# fpga21-serdes-power.net
KiCad netlist of a schematic drawn in Altium Designer
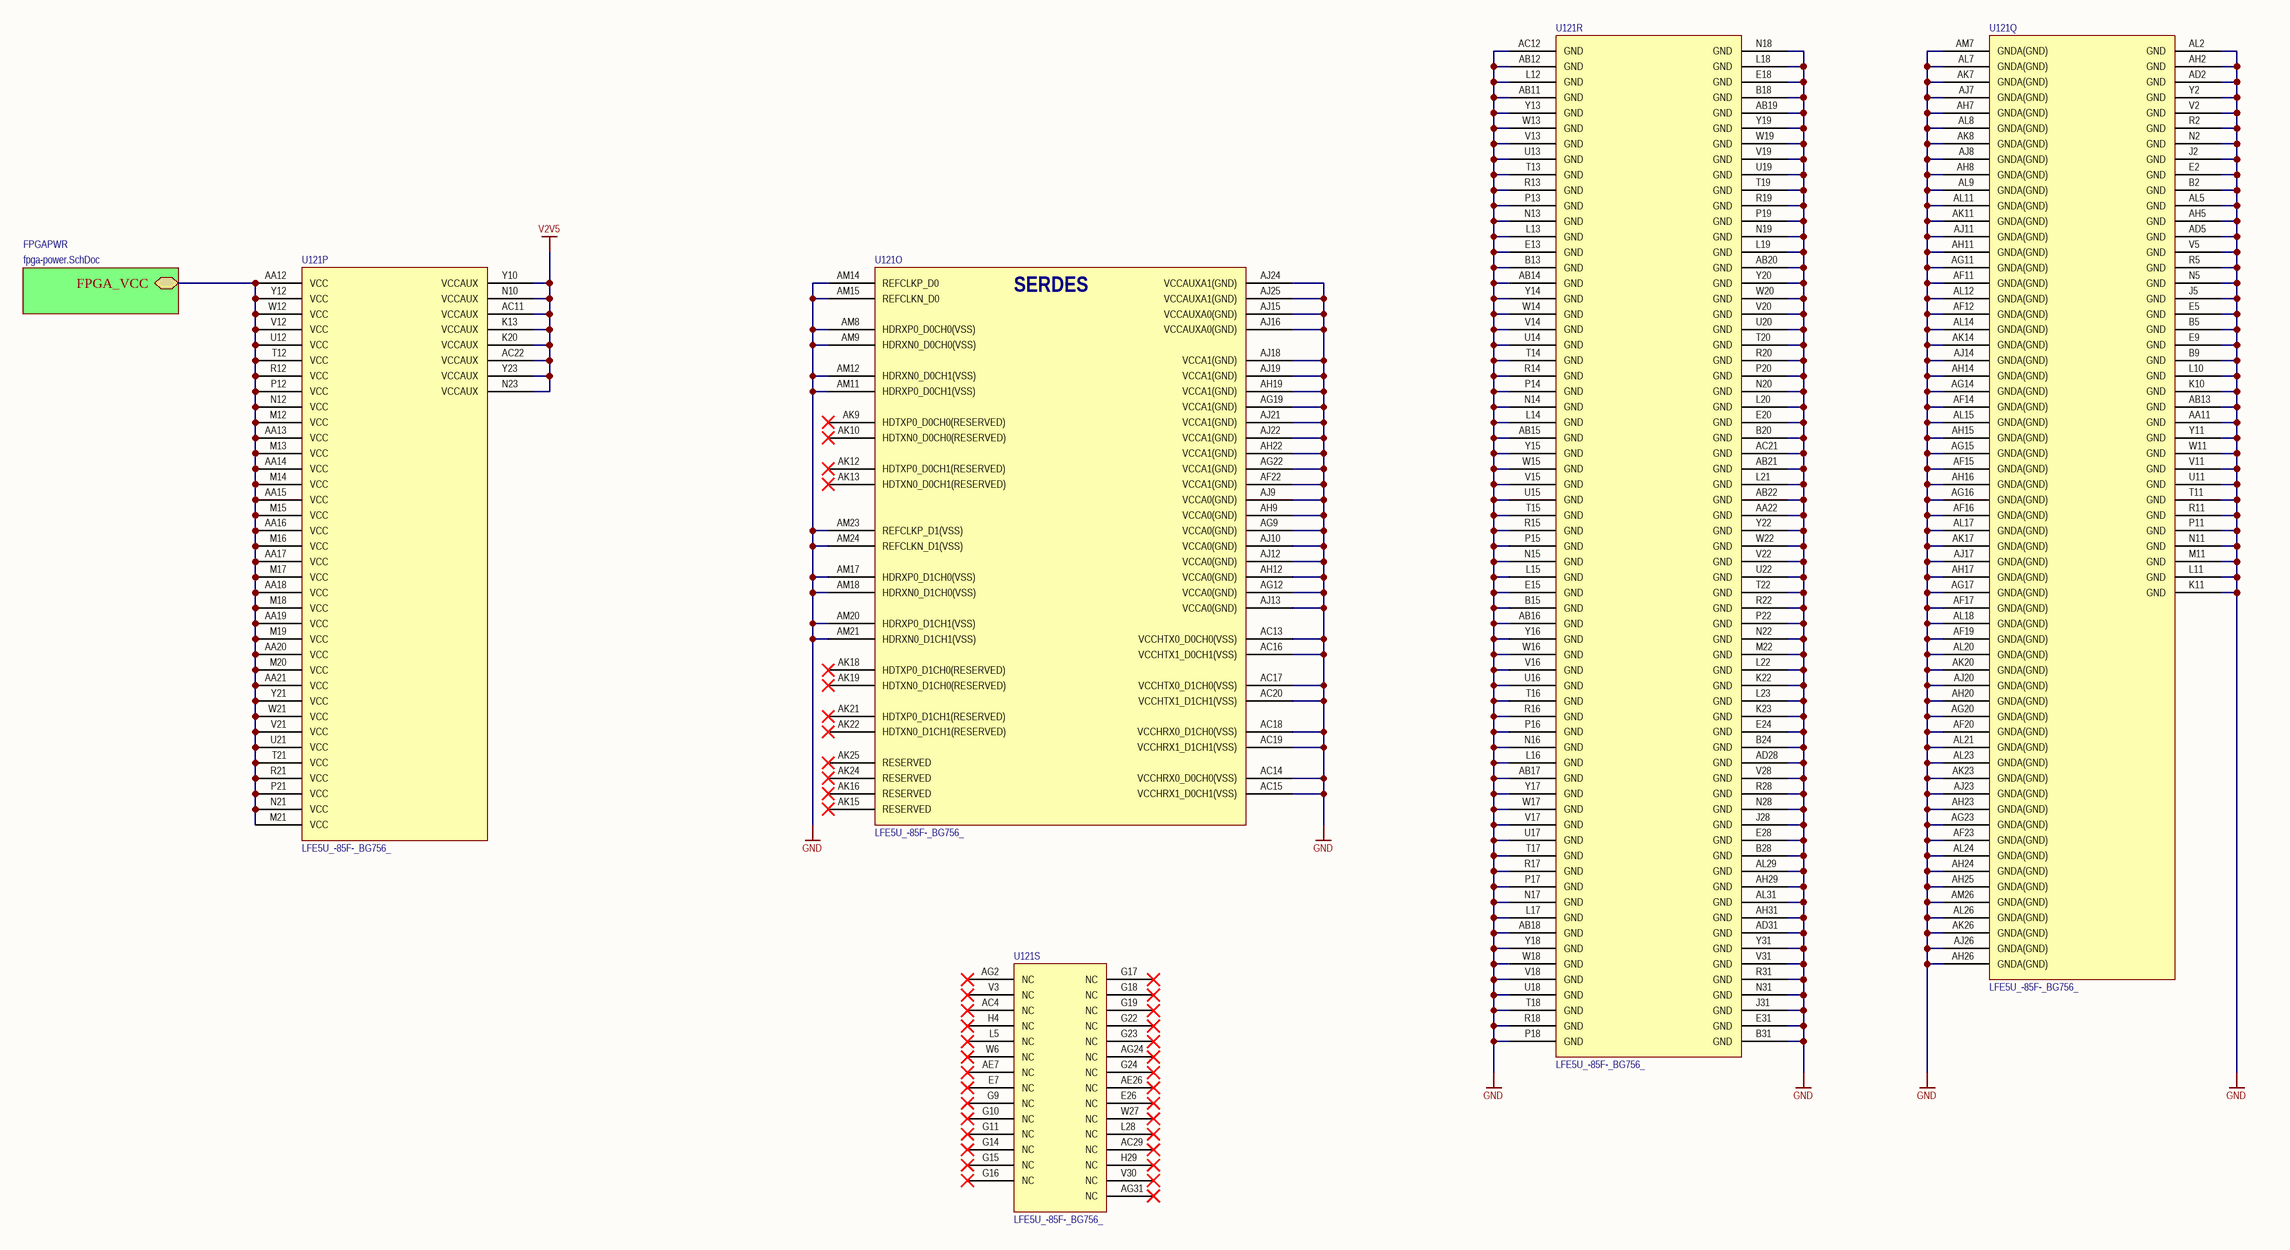
[diagram p0: fpga21-serdes-power.SchDoc]

(export (version "E")
  (design (tool "Eeschema 10.0.6"))
  (components
    (comp (ref "U121")
      (value "LFE5U_-85F-_BG756_")
      (footprint "lattice:caBGA756")
      (description "ECP5 FPGA, 85k LUT, 756-caBGA")
      (fields (field (name "MANUFACTURER") "Lattice Semiconductor"))
      (libsource (lib "lattice") (part "LFE5U_-85F-_BG756_"))
    )
  )
  (nets
    (net (code "1") (name "/FPGA_VCC") (class "Default")
      (node (ref "U121") (pin "AA12") (pinfunction "VCC_AA12") (pintype "power_in"))
      (node (ref "U121") (pin "AA13") (pinfunction "VCC_AA13") (pintype "power_in"))
      (node (ref "U121") (pin "AA14") (pinfunction "VCC_AA14") (pintype "power_in"))
      (node (ref "U121") (pin "AA15") (pinfunction "VCC_AA15") (pintype "power_in"))
      (node (ref "U121") (pin "AA16") (pinfunction "VCC_AA16") (pintype "power_in"))
      (node (ref "U121") (pin "AA17") (pinfunction "VCC_AA17") (pintype "power_in"))
      (node (ref "U121") (pin "AA18") (pinfunction "VCC_AA18") (pintype "power_in"))
      (node (ref "U121") (pin "AA19") (pinfunction "VCC_AA19") (pintype "power_in"))
      (node (ref "U121") (pin "AA20") (pinfunction "VCC_AA20") (pintype "power_in"))
      (node (ref "U121") (pin "AA21") (pinfunction "VCC_AA21") (pintype "power_in"))
      (node (ref "U121") (pin "M12") (pinfunction "VCC_M12") (pintype "power_in"))
      (node (ref "U121") (pin "M13") (pinfunction "VCC_M13") (pintype "power_in"))
      (node (ref "U121") (pin "M14") (pinfunction "VCC_M14") (pintype "power_in"))
      (node (ref "U121") (pin "M15") (pinfunction "VCC_M15") (pintype "power_in"))
      (node (ref "U121") (pin "M16") (pinfunction "VCC_M16") (pintype "power_in"))
      (node (ref "U121") (pin "M17") (pinfunction "VCC_M17") (pintype "power_in"))
      (node (ref "U121") (pin "M18") (pinfunction "VCC_M18") (pintype "power_in"))
      (node (ref "U121") (pin "M19") (pinfunction "VCC_M19") (pintype "power_in"))
      (node (ref "U121") (pin "M20") (pinfunction "VCC_M20") (pintype "power_in"))
      (node (ref "U121") (pin "M21") (pinfunction "VCC_M21") (pintype "power_in"))
      (node (ref "U121") (pin "N12") (pinfunction "VCC_N12") (pintype "power_in"))
      (node (ref "U121") (pin "N21") (pinfunction "VCC_N21") (pintype "power_in"))
      (node (ref "U121") (pin "P12") (pinfunction "VCC_P12") (pintype "power_in"))
      (node (ref "U121") (pin "P21") (pinfunction "VCC_P21") (pintype "power_in"))
      (node (ref "U121") (pin "R12") (pinfunction "VCC_R12") (pintype "power_in"))
      (node (ref "U121") (pin "R21") (pinfunction "VCC_R21") (pintype "power_in"))
      (node (ref "U121") (pin "T12") (pinfunction "VCC_T12") (pintype "power_in"))
      (node (ref "U121") (pin "T21") (pinfunction "VCC_T21") (pintype "power_in"))
      (node (ref "U121") (pin "U12") (pinfunction "VCC_U12") (pintype "power_in"))
      (node (ref "U121") (pin "U21") (pinfunction "VCC_U21") (pintype "power_in"))
      (node (ref "U121") (pin "V12") (pinfunction "VCC_V12") (pintype "power_in"))
      (node (ref "U121") (pin "V21") (pinfunction "VCC_V21") (pintype "power_in"))
      (node (ref "U121") (pin "W12") (pinfunction "VCC_W12") (pintype "power_in"))
      (node (ref "U121") (pin "W21") (pinfunction "VCC_W21") (pintype "power_in"))
      (node (ref "U121") (pin "Y12") (pinfunction "VCC_Y12") (pintype "power_in"))
      (node (ref "U121") (pin "Y21") (pinfunction "VCC_Y21") (pintype "power_in"))
    )
    (net (code "2") (name "GND") (class "Default")
      (node (ref "U121") (pin "AA11") (pinfunction "GND_AA11") (pintype "power_in"))
      (node (ref "U121") (pin "AA22") (pinfunction "GND_AA22") (pintype "power_in"))
      (node (ref "U121") (pin "AB11") (pinfunction "GND_AB11") (pintype "power_in"))
      (node (ref "U121") (pin "AB12") (pinfunction "GND_AB12") (pintype "power_in"))
      (node (ref "U121") (pin "AB13") (pinfunction "GND_AB13") (pintype "power_in"))
      (node (ref "U121") (pin "AB14") (pinfunction "GND_AB14") (pintype "power_in"))
      (node (ref "U121") (pin "AB15") (pinfunction "GND_AB15") (pintype "power_in"))
      (node (ref "U121") (pin "AB16") (pinfunction "GND_AB16") (pintype "power_in"))
      (node (ref "U121") (pin "AB17") (pinfunction "GND_AB17") (pintype "power_in"))
      (node (ref "U121") (pin "AB18") (pinfunction "GND_AB18") (pintype "power_in"))
      (node (ref "U121") (pin "AB19") (pinfunction "GND_AB19") (pintype "power_in"))
      (node (ref "U121") (pin "AB20") (pinfunction "GND_AB20") (pintype "power_in"))
      (node (ref "U121") (pin "AB21") (pinfunction "GND_AB21") (pintype "power_in"))
      (node (ref "U121") (pin "AB22") (pinfunction "GND_AB22") (pintype "power_in"))
      (node (ref "U121") (pin "AC12") (pinfunction "GND_AC12") (pintype "power_in"))
      (node (ref "U121") (pin "AC13") (pinfunction "VCCHTX0_D0CH0(VSS)_AC13") (pintype "power_in"))
      (node (ref "U121") (pin "AC14") (pinfunction "VCCHRX0_D0CH0(VSS)_AC14") (pintype "power_in"))
      (node (ref "U121") (pin "AC15") (pinfunction "VCCHRX1_D0CH1(VSS)_AC15") (pintype "power_in"))
      (node (ref "U121") (pin "AC16") (pinfunction "VCCHTX1_D0CH1(VSS)_AC16") (pintype "power_in"))
      (node (ref "U121") (pin "AC17") (pinfunction "VCCHTX0_D1CH0(VSS)_AC17") (pintype "power_in"))
      (node (ref "U121") (pin "AC18") (pinfunction "VCCHRX0_D1CH0(VSS)_AC18") (pintype "power_in"))
      (node (ref "U121") (pin "AC19") (pinfunction "VCCHRX1_D1CH1(VSS)_AC19") (pintype "power_in"))
      (node (ref "U121") (pin "AC20") (pinfunction "VCCHTX1_D1CH1(VSS)_AC20") (pintype "power_in"))
      (node (ref "U121") (pin "AC21") (pinfunction "GND_AC21") (pintype "power_in"))
      (node (ref "U121") (pin "AD2") (pinfunction "GND_AD2") (pintype "power_in"))
      (node (ref "U121") (pin "AD28") (pinfunction "GND_AD28") (pintype "power_in"))
      (node (ref "U121") (pin "AD31") (pinfunction "GND_AD31") (pintype "power_in"))
      (node (ref "U121") (pin "AD5") (pinfunction "GND_AD5") (pintype "power_in"))
      (node (ref "U121") (pin "AF11") (pinfunction "GNDA(GND)_AF11") (pintype "power_in"))
      (node (ref "U121") (pin "AF12") (pinfunction "GNDA(GND)_AF12") (pintype "power_in"))
      (node (ref "U121") (pin "AF14") (pinfunction "GNDA(GND)_AF14") (pintype "power_in"))
      (node (ref "U121") (pin "AF15") (pinfunction "GNDA(GND)_AF15") (pintype "power_in"))
      (node (ref "U121") (pin "AF16") (pinfunction "GNDA(GND)_AF16") (pintype "power_in"))
      (node (ref "U121") (pin "AF17") (pinfunction "GNDA(GND)_AF17") (pintype "power_in"))
      (node (ref "U121") (pin "AF19") (pinfunction "GNDA(GND)_AF19") (pintype "power_in"))
      (node (ref "U121") (pin "AF20") (pinfunction "GNDA(GND)_AF20") (pintype "power_in"))
      (node (ref "U121") (pin "AF22") (pinfunction "VCCA1(GND)_AF22") (pintype "power_in"))
      (node (ref "U121") (pin "AF23") (pinfunction "GNDA(GND)_AF23") (pintype "power_in"))
      (node (ref "U121") (pin "AG11") (pinfunction "GNDA(GND)_AG11") (pintype "power_in"))
      (node (ref "U121") (pin "AG12") (pinfunction "VCCA0(GND)_AG12") (pintype "power_in"))
      (node (ref "U121") (pin "AG14") (pinfunction "GNDA(GND)_AG14") (pintype "power_in"))
      (node (ref "U121") (pin "AG15") (pinfunction "GNDA(GND)_AG15") (pintype "power_in"))
      (node (ref "U121") (pin "AG16") (pinfunction "GNDA(GND)_AG16") (pintype "power_in"))
      (node (ref "U121") (pin "AG17") (pinfunction "GNDA(GND)_AG17") (pintype "power_in"))
      (node (ref "U121") (pin "AG19") (pinfunction "VCCA1(GND)_AG19") (pintype "power_in"))
      (node (ref "U121") (pin "AG20") (pinfunction "GNDA(GND)_AG20") (pintype "power_in"))
      (node (ref "U121") (pin "AG22") (pinfunction "VCCA1(GND)_AG22") (pintype "power_in"))
      (node (ref "U121") (pin "AG23") (pinfunction "GNDA(GND)_AG23") (pintype "power_in"))
      (node (ref "U121") (pin "AG9") (pinfunction "VCCA0(GND)_AG9") (pintype "power_in"))
      (node (ref "U121") (pin "AH11") (pinfunction "GNDA(GND)_AH11") (pintype "power_in"))
      (node (ref "U121") (pin "AH12") (pinfunction "VCCA0(GND)_AH12") (pintype "power_in"))
      (node (ref "U121") (pin "AH14") (pinfunction "GNDA(GND)_AH14") (pintype "power_in"))
      (node (ref "U121") (pin "AH15") (pinfunction "GNDA(GND)_AH15") (pintype "power_in"))
      (node (ref "U121") (pin "AH16") (pinfunction "GNDA(GND)_AH16") (pintype "power_in"))
      (node (ref "U121") (pin "AH17") (pinfunction "GNDA(GND)_AH17") (pintype "power_in"))
      (node (ref "U121") (pin "AH19") (pinfunction "VCCA1(GND)_AH19") (pintype "power_in"))
      (node (ref "U121") (pin "AH2") (pinfunction "GND_AH2") (pintype "power_in"))
      (node (ref "U121") (pin "AH20") (pinfunction "GNDA(GND)_AH20") (pintype "power_in"))
      (node (ref "U121") (pin "AH22") (pinfunction "VCCA1(GND)_AH22") (pintype "power_in"))
      (node (ref "U121") (pin "AH23") (pinfunction "GNDA(GND)_AH23") (pintype "power_in"))
      (node (ref "U121") (pin "AH24") (pinfunction "GNDA(GND)_AH24") (pintype "power_in"))
      (node (ref "U121") (pin "AH25") (pinfunction "GNDA(GND)_AH25") (pintype "power_in"))
      (node (ref "U121") (pin "AH26") (pinfunction "GNDA(GND)_AH26") (pintype "power_in"))
      (node (ref "U121") (pin "AH29") (pinfunction "GND_AH29") (pintype "power_in"))
      (node (ref "U121") (pin "AH31") (pinfunction "GND_AH31") (pintype "power_in"))
      (node (ref "U121") (pin "AH5") (pinfunction "GND_AH5") (pintype "power_in"))
      (node (ref "U121") (pin "AH7") (pinfunction "GNDA(GND)_AH7") (pintype "power_in"))
      (node (ref "U121") (pin "AH8") (pinfunction "GNDA(GND)_AH8") (pintype "power_in"))
      (node (ref "U121") (pin "AH9") (pinfunction "VCCA0(GND)_AH9") (pintype "power_in"))
      (node (ref "U121") (pin "AJ10") (pinfunction "VCCA0(GND)_AJ10") (pintype "power_in"))
      (node (ref "U121") (pin "AJ11") (pinfunction "GNDA(GND)_AJ11") (pintype "power_in"))
      (node (ref "U121") (pin "AJ12") (pinfunction "VCCA0(GND)_AJ12") (pintype "power_in"))
      (node (ref "U121") (pin "AJ13") (pinfunction "VCCA0(GND)_AJ13") (pintype "power_in"))
      (node (ref "U121") (pin "AJ14") (pinfunction "GNDA(GND)_AJ14") (pintype "power_in"))
      (node (ref "U121") (pin "AJ15") (pinfunction "VCCAUXA0(GND)_AJ15") (pintype "power_in"))
      (node (ref "U121") (pin "AJ16") (pinfunction "VCCAUXA0(GND)_AJ16") (pintype "power_in"))
      (node (ref "U121") (pin "AJ17") (pinfunction "GNDA(GND)_AJ17") (pintype "power_in"))
      (node (ref "U121") (pin "AJ18") (pinfunction "VCCA1(GND)_AJ18") (pintype "power_in"))
      (node (ref "U121") (pin "AJ19") (pinfunction "VCCA1(GND)_AJ19") (pintype "power_in"))
      (node (ref "U121") (pin "AJ20") (pinfunction "GNDA(GND)_AJ20") (pintype "power_in"))
      (node (ref "U121") (pin "AJ21") (pinfunction "VCCA1(GND)_AJ21") (pintype "power_in"))
      (node (ref "U121") (pin "AJ22") (pinfunction "VCCA1(GND)_AJ22") (pintype "power_in"))
      (node (ref "U121") (pin "AJ23") (pinfunction "GNDA(GND)_AJ23") (pintype "power_in"))
      (node (ref "U121") (pin "AJ24") (pinfunction "VCCAUXA1(GND)_AJ24") (pintype "power_in"))
      (node (ref "U121") (pin "AJ25") (pinfunction "VCCAUXA1(GND)_AJ25") (pintype "power_in"))
      (node (ref "U121") (pin "AJ26") (pinfunction "GNDA(GND)_AJ26") (pintype "power_in"))
      (node (ref "U121") (pin "AJ7") (pinfunction "GNDA(GND)_AJ7") (pintype "power_in"))
      (node (ref "U121") (pin "AJ8") (pinfunction "GNDA(GND)_AJ8") (pintype "power_in"))
      (node (ref "U121") (pin "AJ9") (pinfunction "VCCA0(GND)_AJ9") (pintype "power_in"))
      (node (ref "U121") (pin "AK11") (pinfunction "GNDA(GND)_AK11") (pintype "power_in"))
      (node (ref "U121") (pin "AK14") (pinfunction "GNDA(GND)_AK14") (pintype "power_in"))
      (node (ref "U121") (pin "AK17") (pinfunction "GNDA(GND)_AK17") (pintype "power_in"))
      (node (ref "U121") (pin "AK20") (pinfunction "GNDA(GND)_AK20") (pintype "power_in"))
      (node (ref "U121") (pin "AK23") (pinfunction "GNDA(GND)_AK23") (pintype "power_in"))
      (node (ref "U121") (pin "AK26") (pinfunction "GNDA(GND)_AK26") (pintype "power_in"))
      (node (ref "U121") (pin "AK7") (pinfunction "GNDA(GND)_AK7") (pintype "power_in"))
      (node (ref "U121") (pin "AK8") (pinfunction "GNDA(GND)_AK8") (pintype "power_in"))
      (node (ref "U121") (pin "AL11") (pinfunction "GNDA(GND)_AL11") (pintype "power_in"))
      (node (ref "U121") (pin "AL12") (pinfunction "GNDA(GND)_AL12") (pintype "power_in"))
      (node (ref "U121") (pin "AL14") (pinfunction "GNDA(GND)_AL14") (pintype "power_in"))
      (node (ref "U121") (pin "AL15") (pinfunction "GNDA(GND)_AL15") (pintype "power_in"))
      (node (ref "U121") (pin "AL17") (pinfunction "GNDA(GND)_AL17") (pintype "power_in"))
      (node (ref "U121") (pin "AL18") (pinfunction "GNDA(GND)_AL18") (pintype "power_in"))
      (node (ref "U121") (pin "AL2") (pinfunction "GND_AL2") (pintype "power_in"))
      (node (ref "U121") (pin "AL20") (pinfunction "GNDA(GND)_AL20") (pintype "power_in"))
      (node (ref "U121") (pin "AL21") (pinfunction "GNDA(GND)_AL21") (pintype "power_in"))
      (node (ref "U121") (pin "AL23") (pinfunction "GNDA(GND)_AL23") (pintype "power_in"))
      (node (ref "U121") (pin "AL24") (pinfunction "GNDA(GND)_AL24") (pintype "power_in"))
      (node (ref "U121") (pin "AL26") (pinfunction "GNDA(GND)_AL26") (pintype "power_in"))
      (node (ref "U121") (pin "AL29") (pinfunction "GND_AL29") (pintype "power_in"))
      (node (ref "U121") (pin "AL31") (pinfunction "GND_AL31") (pintype "power_in"))
      (node (ref "U121") (pin "AL5") (pinfunction "GND_AL5") (pintype "power_in"))
      (node (ref "U121") (pin "AL7") (pinfunction "GNDA(GND)_AL7") (pintype "power_in"))
      (node (ref "U121") (pin "AL8") (pinfunction "GNDA(GND)_AL8") (pintype "power_in"))
      (node (ref "U121") (pin "AL9") (pinfunction "GNDA(GND)_AL9") (pintype "power_in"))
      (node (ref "U121") (pin "AM11") (pinfunction "HDRXP0_D0CH1(VSS)_AM11") (pintype "passive"))
      (node (ref "U121") (pin "AM12") (pinfunction "HDRXN0_D0CH1(VSS)_AM12") (pintype "passive"))
      (node (ref "U121") (pin "AM14") (pinfunction "REFCLKP_D0_AM14") (pintype "passive"))
      (node (ref "U121") (pin "AM15") (pinfunction "REFCLKN_D0_AM15") (pintype "passive"))
      (node (ref "U121") (pin "AM17") (pinfunction "HDRXP0_D1CH0(VSS)_AM17") (pintype "passive"))
      (node (ref "U121") (pin "AM18") (pinfunction "HDRXN0_D1CH0(VSS)_AM18") (pintype "passive"))
      (node (ref "U121") (pin "AM20") (pinfunction "HDRXP0_D1CH1(VSS)_AM20") (pintype "passive"))
      (node (ref "U121") (pin "AM21") (pinfunction "HDRXN0_D1CH1(VSS)_AM21") (pintype "passive"))
      (node (ref "U121") (pin "AM23") (pinfunction "REFCLKP_D1(VSS)_AM23") (pintype "passive"))
      (node (ref "U121") (pin "AM24") (pinfunction "REFCLKN_D1(VSS)_AM24") (pintype "passive"))
      (node (ref "U121") (pin "AM26") (pinfunction "GNDA(GND)_AM26") (pintype "power_in"))
      (node (ref "U121") (pin "AM7") (pinfunction "GNDA(GND)_AM7") (pintype "power_in"))
      (node (ref "U121") (pin "AM8") (pinfunction "HDRXP0_D0CH0(VSS)_AM8") (pintype "passive"))
      (node (ref "U121") (pin "AM9") (pinfunction "HDRXN0_D0CH0(VSS)_AM9") (pintype "passive"))
      (node (ref "U121") (pin "B13") (pinfunction "GND_B13") (pintype "power_in"))
      (node (ref "U121") (pin "B15") (pinfunction "GND_B15") (pintype "power_in"))
      (node (ref "U121") (pin "B18") (pinfunction "GND_B18") (pintype "power_in"))
      (node (ref "U121") (pin "B2") (pinfunction "GND_B2") (pintype "power_in"))
      (node (ref "U121") (pin "B20") (pinfunction "GND_B20") (pintype "power_in"))
      (node (ref "U121") (pin "B24") (pinfunction "GND_B24") (pintype "power_in"))
      (node (ref "U121") (pin "B28") (pinfunction "GND_B28") (pintype "power_in"))
      (node (ref "U121") (pin "B31") (pinfunction "GND_B31") (pintype "power_in"))
      (node (ref "U121") (pin "B5") (pinfunction "GND_B5") (pintype "power_in"))
      (node (ref "U121") (pin "B9") (pinfunction "GND_B9") (pintype "power_in"))
      (node (ref "U121") (pin "E13") (pinfunction "GND_E13") (pintype "power_in"))
      (node (ref "U121") (pin "E15") (pinfunction "GND_E15") (pintype "power_in"))
      (node (ref "U121") (pin "E18") (pinfunction "GND_E18") (pintype "power_in"))
      (node (ref "U121") (pin "E2") (pinfunction "GND_E2") (pintype "power_in"))
      (node (ref "U121") (pin "E20") (pinfunction "GND_E20") (pintype "power_in"))
      (node (ref "U121") (pin "E24") (pinfunction "GND_E24") (pintype "power_in"))
      (node (ref "U121") (pin "E28") (pinfunction "GND_E28") (pintype "power_in"))
      (node (ref "U121") (pin "E31") (pinfunction "GND_E31") (pintype "power_in"))
      (node (ref "U121") (pin "E5") (pinfunction "GND_E5") (pintype "power_in"))
      (node (ref "U121") (pin "E9") (pinfunction "GND_E9") (pintype "power_in"))
      (node (ref "U121") (pin "J2") (pinfunction "GND_J2") (pintype "power_in"))
      (node (ref "U121") (pin "J28") (pinfunction "GND_J28") (pintype "power_in"))
      (node (ref "U121") (pin "J31") (pinfunction "GND_J31") (pintype "power_in"))
      (node (ref "U121") (pin "J5") (pinfunction "GND_J5") (pintype "power_in"))
      (node (ref "U121") (pin "K10") (pinfunction "GND_K10") (pintype "power_in"))
      (node (ref "U121") (pin "K11") (pinfunction "GND_K11") (pintype "power_in"))
      (node (ref "U121") (pin "K22") (pinfunction "GND_K22") (pintype "power_in"))
      (node (ref "U121") (pin "K23") (pinfunction "GND_K23") (pintype "power_in"))
      (node (ref "U121") (pin "L10") (pinfunction "GND_L10") (pintype "power_in"))
      (node (ref "U121") (pin "L11") (pinfunction "GND_L11") (pintype "power_in"))
      (node (ref "U121") (pin "L12") (pinfunction "GND_L12") (pintype "power_in"))
      (node (ref "U121") (pin "L13") (pinfunction "GND_L13") (pintype "power_in"))
      (node (ref "U121") (pin "L14") (pinfunction "GND_L14") (pintype "power_in"))
      (node (ref "U121") (pin "L15") (pinfunction "GND_L15") (pintype "power_in"))
      (node (ref "U121") (pin "L16") (pinfunction "GND_L16") (pintype "power_in"))
      (node (ref "U121") (pin "L17") (pinfunction "GND_L17") (pintype "power_in"))
      (node (ref "U121") (pin "L18") (pinfunction "GND_L18") (pintype "power_in"))
      (node (ref "U121") (pin "L19") (pinfunction "GND_L19") (pintype "power_in"))
      (node (ref "U121") (pin "L20") (pinfunction "GND_L20") (pintype "power_in"))
      (node (ref "U121") (pin "L21") (pinfunction "GND_L21") (pintype "power_in"))
      (node (ref "U121") (pin "L22") (pinfunction "GND_L22") (pintype "power_in"))
      (node (ref "U121") (pin "L23") (pinfunction "GND_L23") (pintype "power_in"))
      (node (ref "U121") (pin "M11") (pinfunction "GND_M11") (pintype "power_in"))
      (node (ref "U121") (pin "M22") (pinfunction "GND_M22") (pintype "power_in"))
      (node (ref "U121") (pin "N11") (pinfunction "GND_N11") (pintype "power_in"))
      (node (ref "U121") (pin "N13") (pinfunction "GND_N13") (pintype "power_in"))
      (node (ref "U121") (pin "N14") (pinfunction "GND_N14") (pintype "power_in"))
      (node (ref "U121") (pin "N15") (pinfunction "GND_N15") (pintype "power_in"))
      (node (ref "U121") (pin "N16") (pinfunction "GND_N16") (pintype "power_in"))
      (node (ref "U121") (pin "N17") (pinfunction "GND_N17") (pintype "power_in"))
      (node (ref "U121") (pin "N18") (pinfunction "GND_N18") (pintype "power_in"))
      (node (ref "U121") (pin "N19") (pinfunction "GND_N19") (pintype "power_in"))
      (node (ref "U121") (pin "N2") (pinfunction "GND_N2") (pintype "power_in"))
      (node (ref "U121") (pin "N20") (pinfunction "GND_N20") (pintype "power_in"))
      (node (ref "U121") (pin "N22") (pinfunction "GND_N22") (pintype "power_in"))
      (node (ref "U121") (pin "N28") (pinfunction "GND_N28") (pintype "power_in"))
      (node (ref "U121") (pin "N31") (pinfunction "GND_N31") (pintype "power_in"))
      (node (ref "U121") (pin "N5") (pinfunction "GND_N5") (pintype "power_in"))
      (node (ref "U121") (pin "P11") (pinfunction "GND_P11") (pintype "power_in"))
      (node (ref "U121") (pin "P13") (pinfunction "GND_P13") (pintype "power_in"))
      (node (ref "U121") (pin "P14") (pinfunction "GND_P14") (pintype "power_in"))
      (node (ref "U121") (pin "P15") (pinfunction "GND_P15") (pintype "power_in"))
      (node (ref "U121") (pin "P16") (pinfunction "GND_P16") (pintype "power_in"))
      (node (ref "U121") (pin "P17") (pinfunction "GND_P17") (pintype "power_in"))
      (node (ref "U121") (pin "P18") (pinfunction "GND_P18") (pintype "power_in"))
      (node (ref "U121") (pin "P19") (pinfunction "GND_P19") (pintype "power_in"))
      (node (ref "U121") (pin "P20") (pinfunction "GND_P20") (pintype "power_in"))
      (node (ref "U121") (pin "P22") (pinfunction "GND_P22") (pintype "power_in"))
      (node (ref "U121") (pin "R11") (pinfunction "GND_R11") (pintype "power_in"))
      (node (ref "U121") (pin "R13") (pinfunction "GND_R13") (pintype "power_in"))
      (node (ref "U121") (pin "R14") (pinfunction "GND_R14") (pintype "power_in"))
      (node (ref "U121") (pin "R15") (pinfunction "GND_R15") (pintype "power_in"))
      (node (ref "U121") (pin "R16") (pinfunction "GND_R16") (pintype "power_in"))
      (node (ref "U121") (pin "R17") (pinfunction "GND_R17") (pintype "power_in"))
      (node (ref "U121") (pin "R18") (pinfunction "GND_R18") (pintype "power_in"))
      (node (ref "U121") (pin "R19") (pinfunction "GND_R19") (pintype "power_in"))
      (node (ref "U121") (pin "R2") (pinfunction "GND_R2") (pintype "power_in"))
      (node (ref "U121") (pin "R20") (pinfunction "GND_R20") (pintype "power_in"))
      (node (ref "U121") (pin "R22") (pinfunction "GND_R22") (pintype "power_in"))
      (node (ref "U121") (pin "R28") (pinfunction "GND_R28") (pintype "power_in"))
      (node (ref "U121") (pin "R31") (pinfunction "GND_R31") (pintype "power_in"))
      (node (ref "U121") (pin "R5") (pinfunction "GND_R5") (pintype "power_in"))
      (node (ref "U121") (pin "T11") (pinfunction "GND_T11") (pintype "power_in"))
      (node (ref "U121") (pin "T13") (pinfunction "GND_T13") (pintype "power_in"))
      (node (ref "U121") (pin "T14") (pinfunction "GND_T14") (pintype "power_in"))
      (node (ref "U121") (pin "T15") (pinfunction "GND_T15") (pintype "power_in"))
      (node (ref "U121") (pin "T16") (pinfunction "GND_T16") (pintype "power_in"))
      (node (ref "U121") (pin "T17") (pinfunction "GND_T17") (pintype "power_in"))
      (node (ref "U121") (pin "T18") (pinfunction "GND_T18") (pintype "power_in"))
      (node (ref "U121") (pin "T19") (pinfunction "GND_T19") (pintype "power_in"))
      (node (ref "U121") (pin "T20") (pinfunction "GND_T20") (pintype "power_in"))
      (node (ref "U121") (pin "T22") (pinfunction "GND_T22") (pintype "power_in"))
      (node (ref "U121") (pin "U11") (pinfunction "GND_U11") (pintype "power_in"))
      (node (ref "U121") (pin "U13") (pinfunction "GND_U13") (pintype "power_in"))
      (node (ref "U121") (pin "U14") (pinfunction "GND_U14") (pintype "power_in"))
      (node (ref "U121") (pin "U15") (pinfunction "GND_U15") (pintype "power_in"))
      (node (ref "U121") (pin "U16") (pinfunction "GND_U16") (pintype "power_in"))
      (node (ref "U121") (pin "U17") (pinfunction "GND_U17") (pintype "power_in"))
      (node (ref "U121") (pin "U18") (pinfunction "GND_U18") (pintype "power_in"))
      (node (ref "U121") (pin "U19") (pinfunction "GND_U19") (pintype "power_in"))
      (node (ref "U121") (pin "U20") (pinfunction "GND_U20") (pintype "power_in"))
      (node (ref "U121") (pin "U22") (pinfunction "GND_U22") (pintype "power_in"))
      (node (ref "U121") (pin "V11") (pinfunction "GND_V11") (pintype "power_in"))
      (node (ref "U121") (pin "V13") (pinfunction "GND_V13") (pintype "power_in"))
      (node (ref "U121") (pin "V14") (pinfunction "GND_V14") (pintype "power_in"))
      (node (ref "U121") (pin "V15") (pinfunction "GND_V15") (pintype "power_in"))
      (node (ref "U121") (pin "V16") (pinfunction "GND_V16") (pintype "power_in"))
      (node (ref "U121") (pin "V17") (pinfunction "GND_V17") (pintype "power_in"))
      (node (ref "U121") (pin "V18") (pinfunction "GND_V18") (pintype "power_in"))
      (node (ref "U121") (pin "V19") (pinfunction "GND_V19") (pintype "power_in"))
      (node (ref "U121") (pin "V2") (pinfunction "GND_V2") (pintype "power_in"))
      (node (ref "U121") (pin "V20") (pinfunction "GND_V20") (pintype "power_in"))
      (node (ref "U121") (pin "V22") (pinfunction "GND_V22") (pintype "power_in"))
      (node (ref "U121") (pin "V28") (pinfunction "GND_V28") (pintype "power_in"))
      (node (ref "U121") (pin "V31") (pinfunction "GND_V31") (pintype "power_in"))
      (node (ref "U121") (pin "V5") (pinfunction "GND_V5") (pintype "power_in"))
      (node (ref "U121") (pin "W11") (pinfunction "GND_W11") (pintype "power_in"))
      (node (ref "U121") (pin "W13") (pinfunction "GND_W13") (pintype "power_in"))
      (node (ref "U121") (pin "W14") (pinfunction "GND_W14") (pintype "power_in"))
      (node (ref "U121") (pin "W15") (pinfunction "GND_W15") (pintype "power_in"))
      (node (ref "U121") (pin "W16") (pinfunction "GND_W16") (pintype "power_in"))
      (node (ref "U121") (pin "W17") (pinfunction "GND_W17") (pintype "power_in"))
      (node (ref "U121") (pin "W18") (pinfunction "GND_W18") (pintype "power_in"))
      (node (ref "U121") (pin "W19") (pinfunction "GND_W19") (pintype "power_in"))
      (node (ref "U121") (pin "W20") (pinfunction "GND_W20") (pintype "power_in"))
      (node (ref "U121") (pin "W22") (pinfunction "GND_W22") (pintype "power_in"))
      (node (ref "U121") (pin "Y11") (pinfunction "GND_Y11") (pintype "power_in"))
      (node (ref "U121") (pin "Y13") (pinfunction "GND_Y13") (pintype "power_in"))
      (node (ref "U121") (pin "Y14") (pinfunction "GND_Y14") (pintype "power_in"))
      (node (ref "U121") (pin "Y15") (pinfunction "GND_Y15") (pintype "power_in"))
      (node (ref "U121") (pin "Y16") (pinfunction "GND_Y16") (pintype "power_in"))
      (node (ref "U121") (pin "Y17") (pinfunction "GND_Y17") (pintype "power_in"))
      (node (ref "U121") (pin "Y18") (pinfunction "GND_Y18") (pintype "power_in"))
      (node (ref "U121") (pin "Y19") (pinfunction "GND_Y19") (pintype "power_in"))
      (node (ref "U121") (pin "Y2") (pinfunction "GND_Y2") (pintype "power_in"))
      (node (ref "U121") (pin "Y20") (pinfunction "GND_Y20") (pintype "power_in"))
      (node (ref "U121") (pin "Y22") (pinfunction "GND_Y22") (pintype "power_in"))
      (node (ref "U121") (pin "Y31") (pinfunction "GND_Y31") (pintype "power_in"))
    )
    (net (code "3") (name "V2V5") (class "Default")
      (node (ref "U121") (pin "AC11") (pinfunction "VCCAUX_AC11") (pintype "power_in"))
      (node (ref "U121") (pin "AC22") (pinfunction "VCCAUX_AC22") (pintype "power_in"))
      (node (ref "U121") (pin "K13") (pinfunction "VCCAUX_K13") (pintype "power_in"))
      (node (ref "U121") (pin "K20") (pinfunction "VCCAUX_K20") (pintype "power_in"))
      (node (ref "U121") (pin "N10") (pinfunction "VCCAUX_N10") (pintype "power_in"))
      (node (ref "U121") (pin "N23") (pinfunction "VCCAUX_N23") (pintype "power_in"))
      (node (ref "U121") (pin "Y10") (pinfunction "VCCAUX_Y10") (pintype "power_in"))
      (node (ref "U121") (pin "Y23") (pinfunction "VCCAUX_Y23") (pintype "power_in"))
    )
    (net (code "4") (name "unconnected-(U121O-HDTXN0_D0CH0(RESERVED)-PadAK10)") (class "Default")
      (node (ref "U121") (pin "AK10") (pinfunction "HDTXN0_D0CH0(RESERVED)_AK10") (pintype "passive+no_connect"))
    )
    (net (code "5") (name "unconnected-(U121O-HDTXN0_D0CH1(RESERVED)-PadAK13)") (class "Default")
      (node (ref "U121") (pin "AK13") (pinfunction "HDTXN0_D0CH1(RESERVED)_AK13") (pintype "passive+no_connect"))
    )
    (net (code "6") (name "unconnected-(U121O-HDTXN0_D1CH0(RESERVED)-PadAK19)") (class "Default")
      (node (ref "U121") (pin "AK19") (pinfunction "HDTXN0_D1CH0(RESERVED)_AK19") (pintype "passive+no_connect"))
    )
    (net (code "7") (name "unconnected-(U121O-HDTXN0_D1CH1(RESERVED)-PadAK22)") (class "Default")
      (node (ref "U121") (pin "AK22") (pinfunction "HDTXN0_D1CH1(RESERVED)_AK22") (pintype "passive+no_connect"))
    )
    (net (code "8") (name "unconnected-(U121O-HDTXP0_D0CH0(RESERVED)-PadAK9)") (class "Default")
      (node (ref "U121") (pin "AK9") (pinfunction "HDTXP0_D0CH0(RESERVED)_AK9") (pintype "passive+no_connect"))
    )
    (net (code "9") (name "unconnected-(U121O-HDTXP0_D0CH1(RESERVED)-PadAK12)") (class "Default")
      (node (ref "U121") (pin "AK12") (pinfunction "HDTXP0_D0CH1(RESERVED)_AK12") (pintype "passive+no_connect"))
    )
    (net (code "10") (name "unconnected-(U121O-HDTXP0_D1CH0(RESERVED)-PadAK18)") (class "Default")
      (node (ref "U121") (pin "AK18") (pinfunction "HDTXP0_D1CH0(RESERVED)_AK18") (pintype "passive+no_connect"))
    )
    (net (code "11") (name "unconnected-(U121O-HDTXP0_D1CH1(RESERVED)-PadAK21)") (class "Default")
      (node (ref "U121") (pin "AK21") (pinfunction "HDTXP0_D1CH1(RESERVED)_AK21") (pintype "passive+no_connect"))
    )
    (net (code "12") (name "unconnected-(U121O-RESERVED-PadAK15)") (class "Default")
      (node (ref "U121") (pin "AK15") (pinfunction "RESERVED_AK15") (pintype "passive+no_connect"))
    )
    (net (code "13") (name "unconnected-(U121O-RESERVED-PadAK16)") (class "Default")
      (node (ref "U121") (pin "AK16") (pinfunction "RESERVED_AK16") (pintype "passive+no_connect"))
    )
    (net (code "14") (name "unconnected-(U121O-RESERVED-PadAK24)") (class "Default")
      (node (ref "U121") (pin "AK24") (pinfunction "RESERVED_AK24") (pintype "passive+no_connect"))
    )
    (net (code "15") (name "unconnected-(U121O-RESERVED-PadAK25)") (class "Default")
      (node (ref "U121") (pin "AK25") (pinfunction "RESERVED_AK25") (pintype "passive+no_connect"))
    )
    (net (code "16") (name "unconnected-(U121S-NC-PadAC4)") (class "Default")
      (node (ref "U121") (pin "AC4") (pinfunction "NC_AC4") (pintype "passive+no_connect"))
    )
    (net (code "17") (name "unconnected-(U121S-NC-PadAC29)") (class "Default")
      (node (ref "U121") (pin "AC29") (pinfunction "NC_AC29") (pintype "passive+no_connect"))
    )
    (net (code "18") (name "unconnected-(U121S-NC-PadAE7)") (class "Default")
      (node (ref "U121") (pin "AE7") (pinfunction "NC_AE7") (pintype "passive+no_connect"))
    )
    (net (code "19") (name "unconnected-(U121S-NC-PadAE26)") (class "Default")
      (node (ref "U121") (pin "AE26") (pinfunction "NC_AE26") (pintype "passive+no_connect"))
    )
    (net (code "20") (name "unconnected-(U121S-NC-PadAG2)") (class "Default")
      (node (ref "U121") (pin "AG2") (pinfunction "NC_AG2") (pintype "passive+no_connect"))
    )
    (net (code "21") (name "unconnected-(U121S-NC-PadAG24)") (class "Default")
      (node (ref "U121") (pin "AG24") (pinfunction "NC_AG24") (pintype "passive+no_connect"))
    )
    (net (code "22") (name "unconnected-(U121S-NC-PadAG31)") (class "Default")
      (node (ref "U121") (pin "AG31") (pinfunction "NC_AG31") (pintype "passive+no_connect"))
    )
    (net (code "23") (name "unconnected-(U121S-NC-PadE7)") (class "Default")
      (node (ref "U121") (pin "E7") (pinfunction "NC_E7") (pintype "passive+no_connect"))
    )
    (net (code "24") (name "unconnected-(U121S-NC-PadE26)") (class "Default")
      (node (ref "U121") (pin "E26") (pinfunction "NC_E26") (pintype "passive+no_connect"))
    )
    (net (code "25") (name "unconnected-(U121S-NC-PadG9)") (class "Default")
      (node (ref "U121") (pin "G9") (pinfunction "NC_G9") (pintype "passive+no_connect"))
    )
    (net (code "26") (name "unconnected-(U121S-NC-PadG10)") (class "Default")
      (node (ref "U121") (pin "G10") (pinfunction "NC_G10") (pintype "passive+no_connect"))
    )
    (net (code "27") (name "unconnected-(U121S-NC-PadG11)") (class "Default")
      (node (ref "U121") (pin "G11") (pinfunction "NC_G11") (pintype "passive+no_connect"))
    )
    (net (code "28") (name "unconnected-(U121S-NC-PadG14)") (class "Default")
      (node (ref "U121") (pin "G14") (pinfunction "NC_G14") (pintype "passive+no_connect"))
    )
    (net (code "29") (name "unconnected-(U121S-NC-PadG15)") (class "Default")
      (node (ref "U121") (pin "G15") (pinfunction "NC_G15") (pintype "passive+no_connect"))
    )
    (net (code "30") (name "unconnected-(U121S-NC-PadG16)") (class "Default")
      (node (ref "U121") (pin "G16") (pinfunction "NC_G16") (pintype "passive+no_connect"))
    )
    (net (code "31") (name "unconnected-(U121S-NC-PadG17)") (class "Default")
      (node (ref "U121") (pin "G17") (pinfunction "NC_G17") (pintype "passive+no_connect"))
    )
    (net (code "32") (name "unconnected-(U121S-NC-PadG18)") (class "Default")
      (node (ref "U121") (pin "G18") (pinfunction "NC_G18") (pintype "passive+no_connect"))
    )
    (net (code "33") (name "unconnected-(U121S-NC-PadG19)") (class "Default")
      (node (ref "U121") (pin "G19") (pinfunction "NC_G19") (pintype "passive+no_connect"))
    )
    (net (code "34") (name "unconnected-(U121S-NC-PadG22)") (class "Default")
      (node (ref "U121") (pin "G22") (pinfunction "NC_G22") (pintype "passive+no_connect"))
    )
    (net (code "35") (name "unconnected-(U121S-NC-PadG23)") (class "Default")
      (node (ref "U121") (pin "G23") (pinfunction "NC_G23") (pintype "passive+no_connect"))
    )
    (net (code "36") (name "unconnected-(U121S-NC-PadG24)") (class "Default")
      (node (ref "U121") (pin "G24") (pinfunction "NC_G24") (pintype "passive+no_connect"))
    )
    (net (code "37") (name "unconnected-(U121S-NC-PadH4)") (class "Default")
      (node (ref "U121") (pin "H4") (pinfunction "NC_H4") (pintype "passive+no_connect"))
    )
    (net (code "38") (name "unconnected-(U121S-NC-PadH29)") (class "Default")
      (node (ref "U121") (pin "H29") (pinfunction "NC_H29") (pintype "passive+no_connect"))
    )
    (net (code "39") (name "unconnected-(U121S-NC-PadL5)") (class "Default")
      (node (ref "U121") (pin "L5") (pinfunction "NC_L5") (pintype "passive+no_connect"))
    )
    (net (code "40") (name "unconnected-(U121S-NC-PadL28)") (class "Default")
      (node (ref "U121") (pin "L28") (pinfunction "NC_L28") (pintype "passive+no_connect"))
    )
    (net (code "41") (name "unconnected-(U121S-NC-PadV3)") (class "Default")
      (node (ref "U121") (pin "V3") (pinfunction "NC_V3") (pintype "passive+no_connect"))
    )
    (net (code "42") (name "unconnected-(U121S-NC-PadV30)") (class "Default")
      (node (ref "U121") (pin "V30") (pinfunction "NC_V30") (pintype "passive+no_connect"))
    )
    (net (code "43") (name "unconnected-(U121S-NC-PadW6)") (class "Default")
      (node (ref "U121") (pin "W6") (pinfunction "NC_W6") (pintype "passive+no_connect"))
    )
    (net (code "44") (name "unconnected-(U121S-NC-PadW27)") (class "Default")
      (node (ref "U121") (pin "W27") (pinfunction "NC_W27") (pintype "passive+no_connect"))
    )
  )
)
